# Control_Interface_Board.net
KiCad netlist of a schematic drawn in Altium Designer
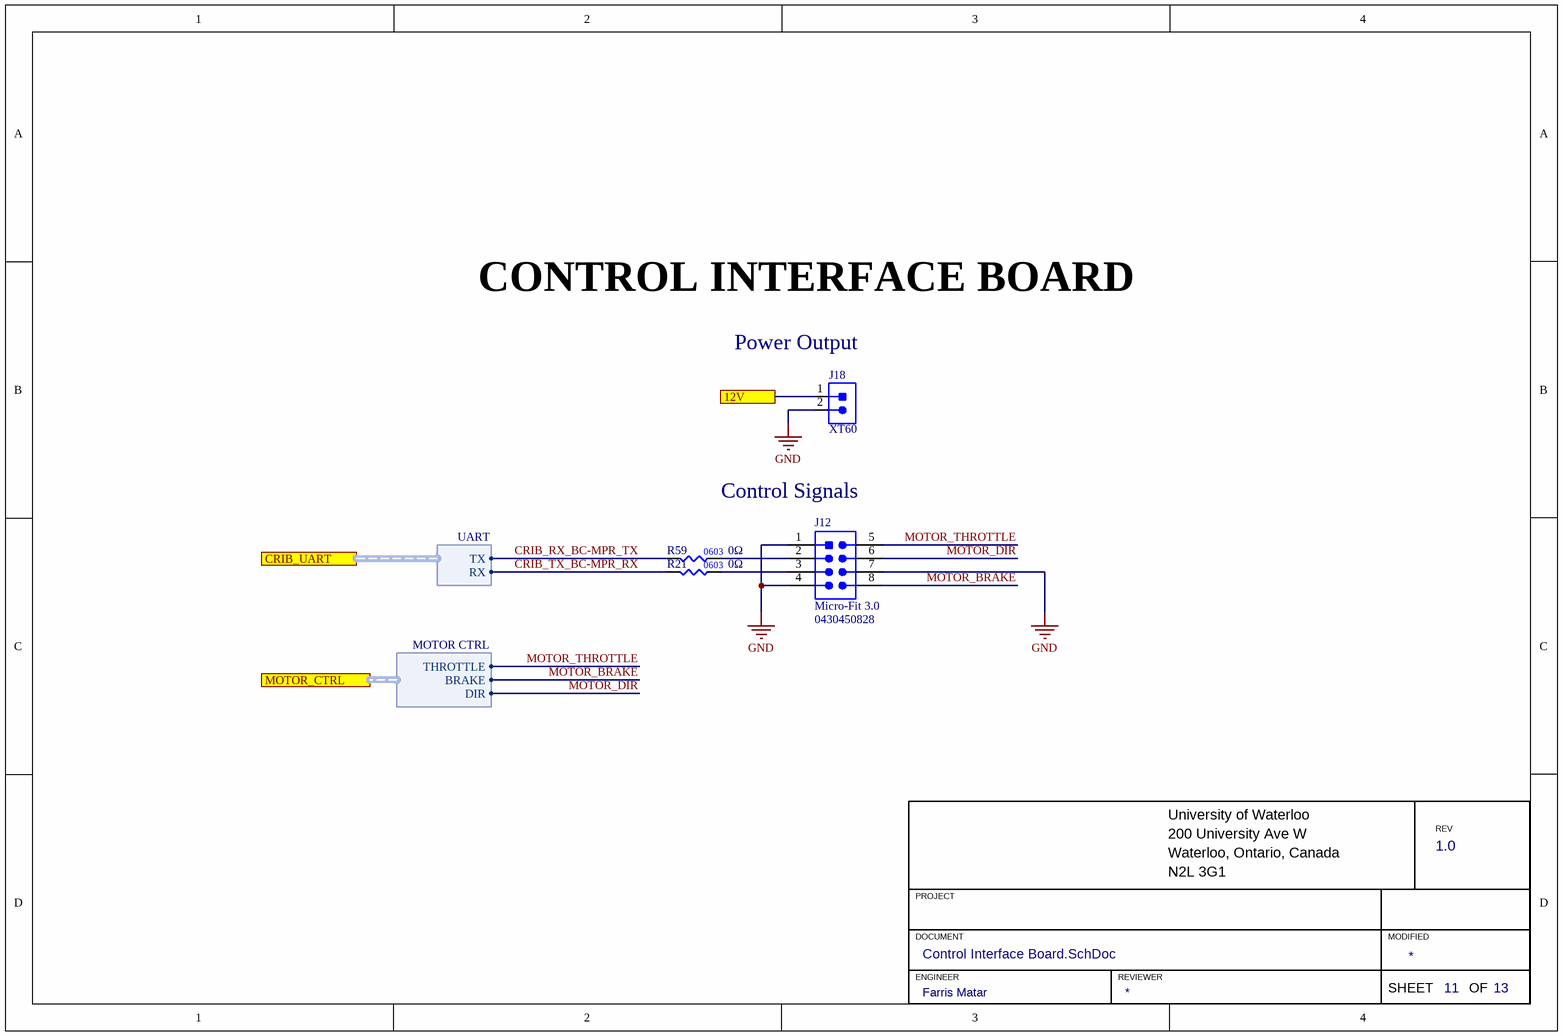
[diagram p0: Control Interface Board.SchDoc]

(export (version "E")
  (design (tool "Eeschema 10.0.6"))
  (components
    (comp (ref "J12")
      (value "0430450828")
      (footprint "MOLEX-0430450828")
      (description "CONN HEADER VERT 8POS 3MM")
      (fields
        (field (name "FAMILY") "Micro-Fit 3.0")
        (field (name "MANUFACTURER PART NUMBER 1") "0430450828")
      )
      (libsource (lib "Personal_Schematic_Library_2022") (part "CON_MOLEX-HDR_4x2_TH"))
    )
    (comp (ref "J18")
      (value "CON_2POS_XT60")
      (footprint "XT60")
      (description "XT60 CONNECTORS MALE/FEMALE PAIR")
      (fields (field (name "PACKAGE/FOOTPRINT") "XT60"))
      (libsource (lib "Personal_Schematic_Library_2022") (part "CON_2POS_XT60"))
    )
    (comp (ref "R21")
      (value "0Ω")
      (footprint "RES0603")
      (description "RES 0 OHM JUMPER 1/10W 0603")
      (fields (field (name "Comment") "RES_0Ω_0603"))
      (libsource (lib "Personal_Schematic_Library_2022") (part "RES_0Ω_0603"))
    )
    (comp (ref "R59")
      (value "0Ω")
      (footprint "RES0603")
      (description "RES 0 OHM JUMPER 1/10W 0603")
      (fields (field (name "Comment") "RES_0Ω_0603"))
      (libsource (lib "Personal_Schematic_Library_2022") (part "RES_0Ω_0603"))
    )
  )
  (nets
    (net (code "4") (name "/12V") (class "Default")
      (node (ref "J18") (pin "1") (pinfunction "1_1") (pintype "passive"))
    )
    (net (code "5") (name "/CRIB_RX_BC-MPR_TX") (class "Default")
      (node (ref "R59") (pin "1") (pinfunction "1_1") (pintype "passive"))
    )
    (net (code "6") (name "/CRIB_TX_BC-MPR_RX") (class "Default")
      (node (ref "R21") (pin "1") (pinfunction "1_1") (pintype "passive"))
    )
    (net (code "7") (name "/MOTOR_BRAKE") (class "Default")
      (node (ref "J12") (pin "8") (pinfunction "8_8") (pintype "passive"))
    )
    (net (code "8") (name "/MOTOR_DIR") (class "Default")
      (node (ref "J12") (pin "6") (pinfunction "6_6") (pintype "passive"))
    )
    (net (code "9") (name "/MOTOR_THROTTLE") (class "Default")
      (node (ref "J12") (pin "5") (pinfunction "5_5") (pintype "passive"))
    )
    (net (code "12") (name "GND") (class "Default")
      (node (ref "J12") (pin "1") (pinfunction "1_1") (pintype "passive"))
      (node (ref "J12") (pin "4") (pinfunction "4_4") (pintype "passive"))
      (node (ref "J12") (pin "7") (pinfunction "7_7") (pintype "passive"))
      (node (ref "J18") (pin "2") (pinfunction "2_2") (pintype "passive"))
    )
    (net (code "13") (name "Net-(J12-Pad2)") (class "Default")
      (node (ref "J12") (pin "2") (pinfunction "2_2") (pintype "passive"))
      (node (ref "R59") (pin "2") (pinfunction "2_2") (pintype "passive"))
    )
    (net (code "14") (name "Net-(J12-Pad3)") (class "Default")
      (node (ref "J12") (pin "3") (pinfunction "3_3") (pintype "passive"))
      (node (ref "R21") (pin "2") (pinfunction "2_2") (pintype "passive"))
    )
  )
)
